# Dveri_Termotunnel_TRIAC.net
KiCad netlist of a schematic drawn in EAGLE
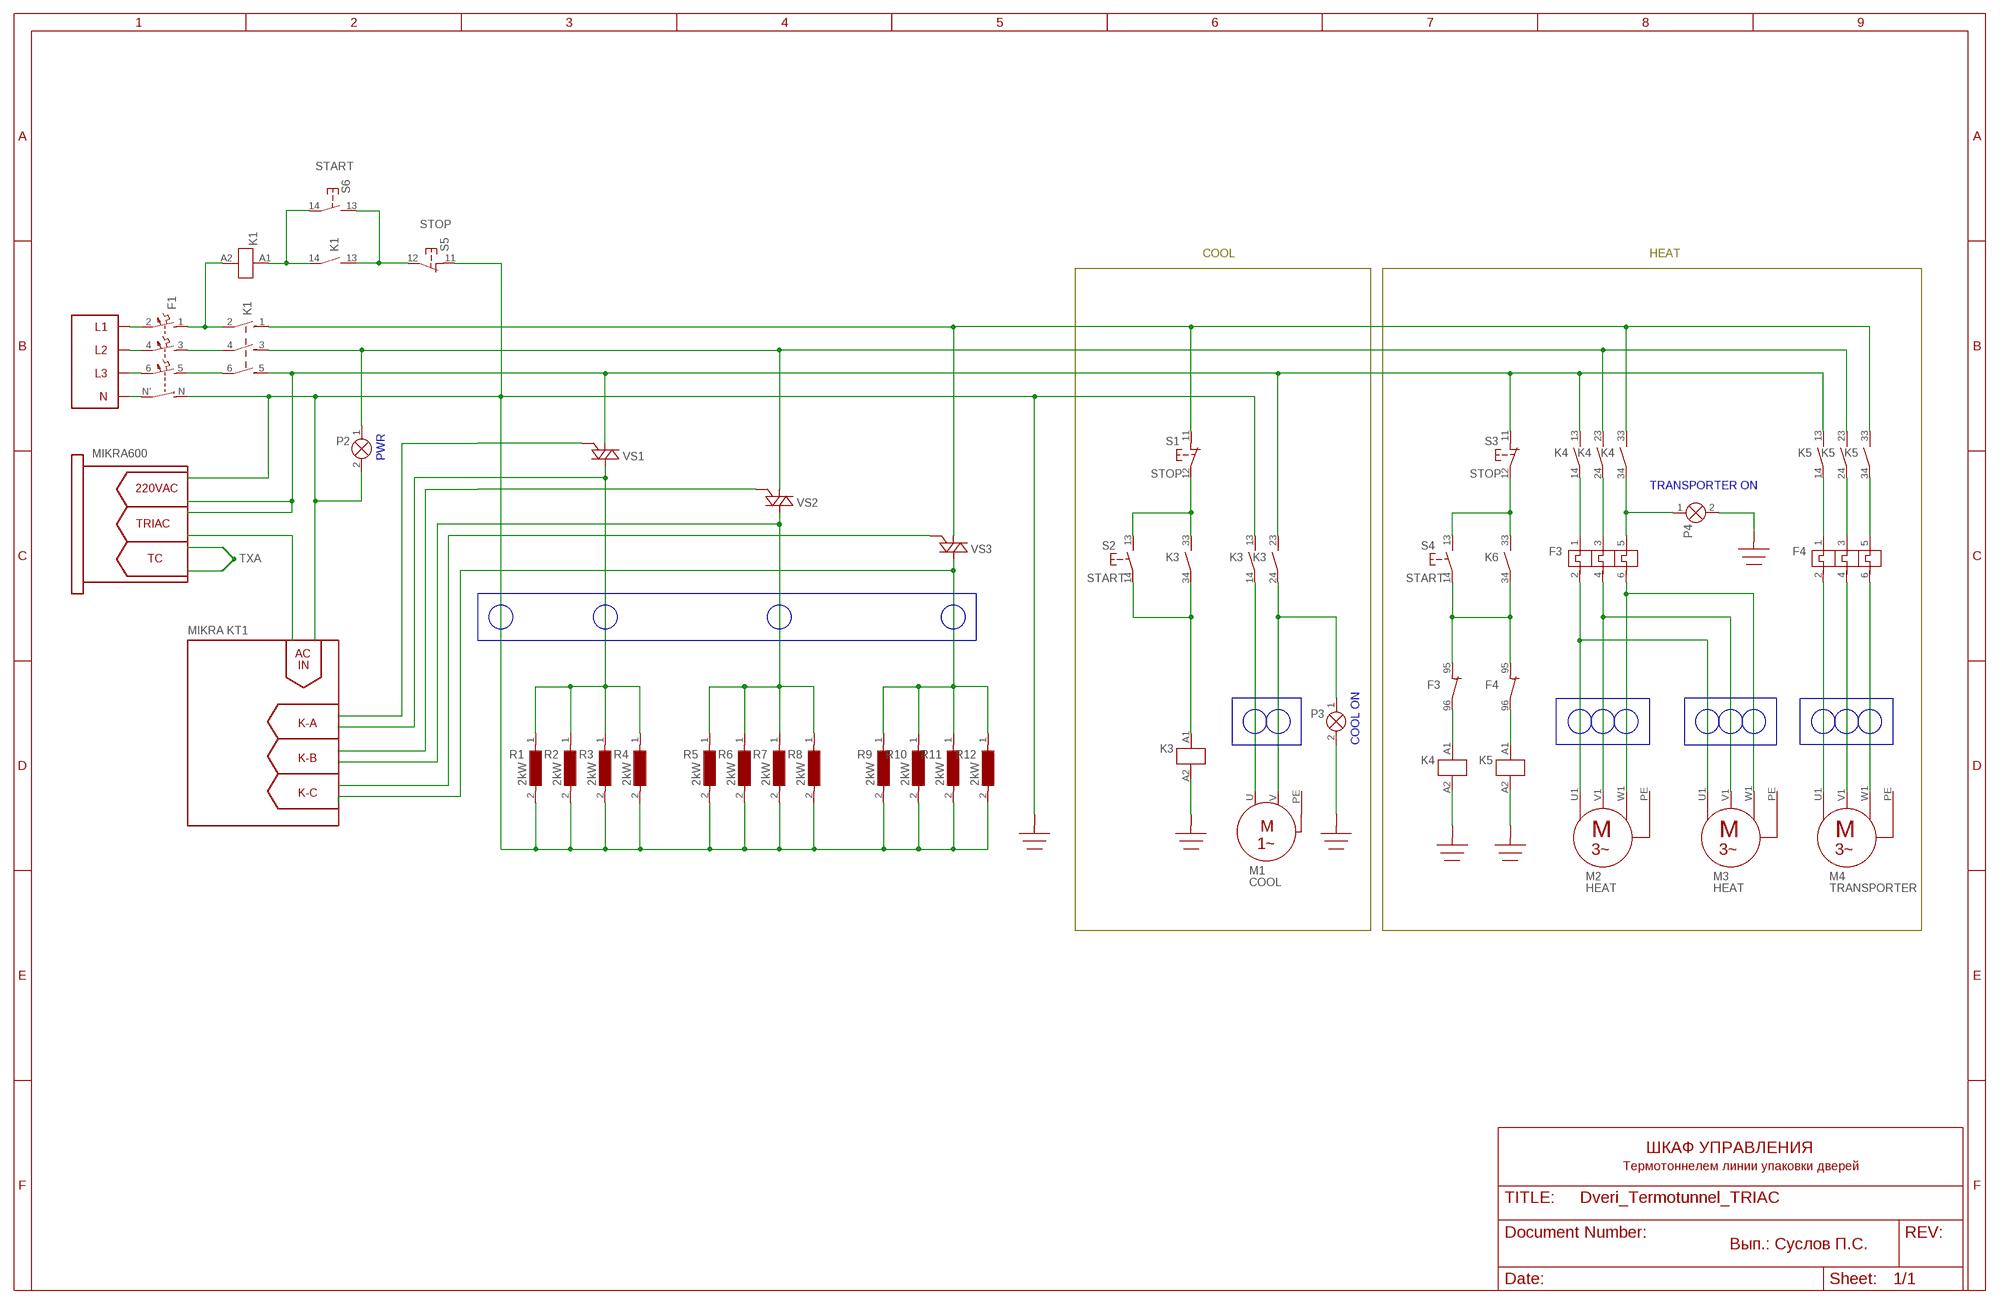
[diagram p0: schematic, sheet 1]

(export (version "E")
  (design (tool "Eeschema 10.0.6"))
  (components
    (comp (ref "F1")
      (value "LEITUNGSSCHUTZSCHALTER_4-POL")
      (footprint "eagle-import:LEITUNGSSCHUTZSCHALTER_4-POL")
      (libsource (lib "eagle-import") (part "LEITUNGSSCHUTZSCHALTER_4-POL"))
    )
    (comp (ref "F3")
      (value "MOTORSCHUTZSCHALTER_3-POL_THERM_AUSLOESUNG_HILFSKONTAKTE")
      (footprint "eagle-import:MOTORSCHUTZSCHALTER_3-POL_THERM_AUSLOESUNG_HILFSKONTAKT_95_96_97_98")
      (libsource (lib "eagle-import") (part "MOTORSCHUTZSCHALTER_3-POL_THERM_AUSLOESUNG_HILFSKONTAKTE"))
    )
    (comp (ref "F4")
      (value "MOTORSCHUTZSCHALTER_3-POL_THERM_AUSLOESUNG_HILFSKONTAKTE")
      (footprint "eagle-import:MOTORSCHUTZSCHALTER_3-POL_THERM_AUSLOESUNG_HILFSKONTAKT_95_96_97_98")
      (libsource (lib "eagle-import") (part "MOTORSCHUTZSCHALTER_3-POL_THERM_AUSLOESUNG_HILFSKONTAKTE"))
    )
    (comp (ref "K1")
      (value "HAUPTSCHUETZ_3-POL_HILFSKONTAKT_13-14")
      (footprint "eagle-import:HAUPTSCHUETZ_3-POL+HILFSKONTAKT_13-14")
      (libsource (lib "eagle-import") (part "HAUPTSCHUETZ_3-POL_HILFSKONTAKT_13-14"))
    )
    (comp (ref "K3")
      (value "HILFSSCHUETZ_13-14_23-24_33_34")
      (footprint "eagle-import:HILFSSCHUETZ_13-14_23-24_33_34")
      (libsource (lib "eagle-import") (part "HILFSSCHUETZ_13-14_23-24_33_34"))
    )
    (comp (ref "K4")
      (value "HILFSSCHUETZ_13-14_23-24_33_34")
      (footprint "eagle-import:HILFSSCHUETZ_13-14_23-24_33_34")
      (libsource (lib "eagle-import") (part "HILFSSCHUETZ_13-14_23-24_33_34"))
    )
    (comp (ref "K5")
      (value "HILFSSCHUETZ_13-14_23-24_33_34")
      (footprint "eagle-import:HILFSSCHUETZ_13-14_23-24_33_34")
      (libsource (lib "eagle-import") (part "HILFSSCHUETZ_13-14_23-24_33_34"))
    )
    (comp (ref "K6")
      (value "HILFSSCHUETZ_13-14_23-24_33_34")
      (footprint "eagle-import:HILFSSCHUETZ_13-14_23-24_33_34")
      (libsource (lib "eagle-import") (part "HILFSSCHUETZ_13-14_23-24_33_34"))
    )
    (comp (ref "M1")
      (value "COOL")
      (footprint "eagle-import:MOTOR_1-PHASEN")
      (libsource (lib "eagle-import") (part "MOTOR_1-PHASEN"))
    )
    (comp (ref "M2")
      (value "HEAT")
      (footprint "eagle-import:MOTOR_3-POL_PE")
      (libsource (lib "eagle-import") (part "MOTOR_3-POL_PE"))
    )
    (comp (ref "M3")
      (value "HEAT")
      (footprint "eagle-import:MOTOR_3-POL_PE")
      (libsource (lib "eagle-import") (part "MOTOR_3-POL_PE"))
    )
    (comp (ref "M4")
      (value "TRANSPORTER")
      (footprint "eagle-import:MOTOR_3-POL_PE")
      (libsource (lib "eagle-import") (part "MOTOR_3-POL_PE"))
    )
    (comp (ref "P2")
      (value "SIGNALLAMPE")
      (footprint "eagle-import:LAMPE")
      (libsource (lib "eagle-import") (part "SIGNALLAMPE"))
    )
    (comp (ref "P3")
      (value "SIGNALLAMPE")
      (footprint "eagle-import:LAMPE")
      (libsource (lib "eagle-import") (part "SIGNALLAMPE"))
    )
    (comp (ref "P4")
      (value "SIGNALLAMPE")
      (footprint "eagle-import:LAMPE")
      (libsource (lib "eagle-import") (part "SIGNALLAMPE"))
    )
    (comp (ref "R1")
      (value "2kW")
      (footprint "eagle-import:WICKLUNG")
      (libsource (lib "eagle-import") (part "SPULE"))
    )
    (comp (ref "R2")
      (value "2kW")
      (footprint "eagle-import:WICKLUNG")
      (libsource (lib "eagle-import") (part "SPULE"))
    )
    (comp (ref "R3")
      (value "2kW")
      (footprint "eagle-import:WICKLUNG")
      (libsource (lib "eagle-import") (part "SPULE"))
    )
    (comp (ref "R4")
      (value "2kW")
      (footprint "eagle-import:WICKLUNG")
      (libsource (lib "eagle-import") (part "SPULE"))
    )
    (comp (ref "R5")
      (value "2kW")
      (footprint "eagle-import:WICKLUNG")
      (libsource (lib "eagle-import") (part "SPULE"))
    )
    (comp (ref "R6")
      (value "2kW")
      (footprint "eagle-import:WICKLUNG")
      (libsource (lib "eagle-import") (part "SPULE"))
    )
    (comp (ref "R7")
      (value "2kW")
      (footprint "eagle-import:WICKLUNG")
      (libsource (lib "eagle-import") (part "SPULE"))
    )
    (comp (ref "R8")
      (value "2kW")
      (footprint "eagle-import:WICKLUNG")
      (libsource (lib "eagle-import") (part "SPULE"))
    )
    (comp (ref "R9")
      (value "2kW")
      (footprint "eagle-import:WICKLUNG")
      (libsource (lib "eagle-import") (part "SPULE"))
    )
    (comp (ref "R10")
      (value "2kW")
      (footprint "eagle-import:WICKLUNG")
      (libsource (lib "eagle-import") (part "SPULE"))
    )
    (comp (ref "R11")
      (value "2kW")
      (footprint "eagle-import:WICKLUNG")
      (libsource (lib "eagle-import") (part "SPULE"))
    )
    (comp (ref "R12")
      (value "2kW")
      (footprint "eagle-import:WICKLUNG")
      (libsource (lib "eagle-import") (part "SPULE"))
    )
    (comp (ref "S1")
      (value "OEFFNER_TASTSCHALTER")
      (footprint "eagle-import:OEFFNER_TASTSCHALTER")
      (libsource (lib "eagle-import") (part "OEFFNER_TASTSCHALTER"))
    )
    (comp (ref "S2")
      (value "SCHLIESSER_TASTSCHALTER")
      (footprint "eagle-import:SCHLIESSER_TASTSCHALTER")
      (libsource (lib "eagle-import") (part "SCHLIESSER_TASTSCHALTER"))
    )
    (comp (ref "S3")
      (value "OEFFNER_TASTSCHALTER")
      (footprint "eagle-import:OEFFNER_TASTSCHALTER")
      (libsource (lib "eagle-import") (part "OEFFNER_TASTSCHALTER"))
    )
    (comp (ref "S4")
      (value "SCHLIESSER_TASTSCHALTER")
      (footprint "eagle-import:SCHLIESSER_TASTSCHALTER")
      (libsource (lib "eagle-import") (part "SCHLIESSER_TASTSCHALTER"))
    )
    (comp (ref "S5")
      (value "OEFFNER_TASTSCHALTER")
      (footprint "eagle-import:OEFFNER_TASTSCHALTER")
      (libsource (lib "eagle-import") (part "OEFFNER_TASTSCHALTER"))
    )
    (comp (ref "S6")
      (value "SCHLIESSER_TASTSCHALTER")
      (footprint "eagle-import:SCHLIESSER_TASTSCHALTER")
      (libsource (lib "eagle-import") (part "SCHLIESSER_TASTSCHALTER"))
    )
    (comp (ref "VS1")
      (value "TRIAC")
      (footprint "eagle-import:TRIAC")
      (libsource (lib "eagle-import") (part "TRIAC"))
    )
    (comp (ref "VS2")
      (value "TRIAC")
      (footprint "eagle-import:TRIAC")
      (libsource (lib "eagle-import") (part "TRIAC"))
    )
    (comp (ref "VS3")
      (value "TRIAC")
      (footprint "eagle-import:TRIAC")
      (libsource (lib "eagle-import") (part "TRIAC"))
    )
    (comp (ref "X1")
      (value "ERDE_ALLGEMEIN")
      (footprint "eagle-import:ERDE_ALLGEMEIN")
      (libsource (lib "eagle-import") (part "ERDE_ALLGEMEIN"))
    )
    (comp (ref "X2")
      (value "ERDE_ALLGEMEIN")
      (footprint "eagle-import:ERDE_ALLGEMEIN")
      (libsource (lib "eagle-import") (part "ERDE_ALLGEMEIN"))
    )
    (comp (ref "X3")
      (value "ERDE_ALLGEMEIN")
      (footprint "eagle-import:ERDE_ALLGEMEIN")
      (libsource (lib "eagle-import") (part "ERDE_ALLGEMEIN"))
    )
    (comp (ref "X4")
      (value "ERDE_ALLGEMEIN")
      (footprint "eagle-import:ERDE_ALLGEMEIN")
      (libsource (lib "eagle-import") (part "ERDE_ALLGEMEIN"))
    )
    (comp (ref "X5")
      (value "ERDE_ALLGEMEIN")
      (footprint "eagle-import:ERDE_ALLGEMEIN")
      (libsource (lib "eagle-import") (part "ERDE_ALLGEMEIN"))
    )
    (comp (ref "X7")
      (value "ERDE_ALLGEMEIN")
      (footprint "eagle-import:ERDE_ALLGEMEIN")
      (libsource (lib "eagle-import") (part "ERDE_ALLGEMEIN"))
    )
  )
  (nets
    (net (code "1") (name "/N") (class "Default")
      (node (ref "F1") (pin "N") (pinfunction "N_N") (pintype "passive"))
      (node (ref "K3") (pin "13") (pinfunction "3_13") (pintype "passive"))
      (node (ref "K3") (pin "A2") (pinfunction "A2_A2") (pintype "input"))
      (node (ref "K4") (pin "A2") (pinfunction "A2_A2") (pintype "input"))
      (node (ref "K5") (pin "A2") (pinfunction "A2_A2") (pintype "input"))
      (node (ref "P2") (pin "2") (pinfunction "X2_2") (pintype "passive"))
      (node (ref "P3") (pin "2") (pinfunction "X2_2") (pintype "passive"))
      (node (ref "P4") (pin "2") (pinfunction "X2_2") (pintype "passive"))
      (node (ref "R1") (pin "2") (pinfunction "2_2") (pintype "passive"))
      (node (ref "R10") (pin "2") (pinfunction "2_2") (pintype "passive"))
      (node (ref "R11") (pin "2") (pinfunction "2_2") (pintype "passive"))
      (node (ref "R12") (pin "2") (pinfunction "2_2") (pintype "passive"))
      (node (ref "R2") (pin "2") (pinfunction "2_2") (pintype "passive"))
      (node (ref "R3") (pin "2") (pinfunction "2_2") (pintype "passive"))
      (node (ref "R4") (pin "2") (pinfunction "2_2") (pintype "passive"))
      (node (ref "R5") (pin "2") (pinfunction "2_2") (pintype "passive"))
      (node (ref "R6") (pin "2") (pinfunction "2_2") (pintype "passive"))
      (node (ref "R7") (pin "2") (pinfunction "2_2") (pintype "passive"))
      (node (ref "R8") (pin "2") (pinfunction "2_2") (pintype "passive"))
      (node (ref "R9") (pin "2") (pinfunction "2_2") (pintype "passive"))
      (node (ref "S5") (pin "11") (pinfunction "1_11") (pintype "input"))
      (node (ref "X1") (pin "1") (pinfunction "PE_1") (pintype "passive"))
      (node (ref "X2") (pin "1") (pinfunction "PE_1") (pintype "passive"))
      (node (ref "X3") (pin "1") (pinfunction "PE_1") (pintype "passive"))
      (node (ref "X4") (pin "1") (pinfunction "PE_1") (pintype "passive"))
      (node (ref "X5") (pin "1") (pinfunction "PE_1") (pintype "passive"))
      (node (ref "X7") (pin "1") (pinfunction "PE_1") (pintype "passive"))
    )
    (net (code "2") (name "Net-(F1-N-PadN')") (class "Default")
      (node (ref "F1") (pin "N'") (pinfunction "N_N'") (pintype "passive"))
    )
    (net (code "3") (name "Net-(F1-Pad1)") (class "Default")
      (node (ref "F1") (pin "1") (pinfunction "1_1") (pintype "passive"))
      (node (ref "K1") (pin "2") (pinfunction "2_2") (pintype "passive"))
      (node (ref "K1") (pin "A2") (pinfunction "A2_A2") (pintype "input"))
    )
    (net (code "4") (name "Net-(F1-Pad2)") (class "Default")
      (node (ref "F1") (pin "2") (pinfunction "2_2") (pintype "passive"))
    )
    (net (code "5") (name "Net-(F1-Pad3)") (class "Default")
      (node (ref "F1") (pin "3") (pinfunction "3_3") (pintype "passive"))
      (node (ref "K1") (pin "4") (pinfunction "4_4") (pintype "passive"))
    )
    (net (code "6") (name "Net-(F1-Pad4)") (class "Default")
      (node (ref "F1") (pin "4") (pinfunction "4_4") (pintype "passive"))
    )
    (net (code "7") (name "Net-(F1-Pad5)") (class "Default")
      (node (ref "F1") (pin "5") (pinfunction "5_5") (pintype "passive"))
      (node (ref "K1") (pin "6") (pinfunction "6_6") (pintype "passive"))
    )
    (net (code "8") (name "Net-(F1-Pad6)") (class "Default")
      (node (ref "F1") (pin "6") (pinfunction "6_6") (pintype "passive"))
    )
    (net (code "9") (name "Net-(F3-Pad2)") (class "Default")
      (node (ref "F3") (pin "2") (pinfunction "2_2") (pintype "passive"))
      (node (ref "M2") (pin "U1") (pinfunction "U1_U1") (pintype "passive"))
      (node (ref "M3") (pin "U1") (pinfunction "U1_U1") (pintype "passive"))
    )
    (net (code "10") (name "Net-(F3-Pad4)") (class "Default")
      (node (ref "F3") (pin "4") (pinfunction "4_4") (pintype "passive"))
      (node (ref "M2") (pin "V1") (pinfunction "V1_V1") (pintype "passive"))
      (node (ref "M3") (pin "V1") (pinfunction "V1_V1") (pintype "passive"))
    )
    (net (code "11") (name "Net-(F3-Pad6)") (class "Default")
      (node (ref "F3") (pin "6") (pinfunction "6_6") (pintype "passive"))
      (node (ref "M2") (pin "W1") (pinfunction "W1_W1") (pintype "passive"))
      (node (ref "M3") (pin "W1") (pinfunction "W1_W1") (pintype "passive"))
    )
    (net (code "12") (name "Net-(F3-Pad96)") (class "Default")
      (node (ref "F3") (pin "96") (pinfunction "96_96") (pintype "passive"))
      (node (ref "K4") (pin "A1") (pinfunction "A1_A1") (pintype "input"))
    )
    (net (code "13") (name "Net-(F4-Pad2)") (class "Default")
      (node (ref "F4") (pin "2") (pinfunction "2_2") (pintype "passive"))
      (node (ref "M4") (pin "U1") (pinfunction "U1_U1") (pintype "passive"))
    )
    (net (code "14") (name "Net-(F4-Pad4)") (class "Default")
      (node (ref "F4") (pin "4") (pinfunction "4_4") (pintype "passive"))
      (node (ref "M4") (pin "V1") (pinfunction "V1_V1") (pintype "passive"))
    )
    (net (code "15") (name "Net-(F4-Pad6)") (class "Default")
      (node (ref "F4") (pin "6") (pinfunction "6_6") (pintype "passive"))
      (node (ref "M4") (pin "W1") (pinfunction "W1_W1") (pintype "passive"))
    )
    (net (code "16") (name "Net-(F4-Pad96)") (class "Default")
      (node (ref "F4") (pin "96") (pinfunction "96_96") (pintype "passive"))
      (node (ref "K5") (pin "A1") (pinfunction "A1_A1") (pintype "input"))
    )
    (net (code "17") (name "Net-(K1B-3)") (class "Default")
      (node (ref "K1") (pin "13") (pinfunction "3_13") (pintype "passive"))
      (node (ref "S5") (pin "12") (pinfunction "2_12") (pintype "input"))
      (node (ref "S6") (pin "13") (pinfunction "3_13") (pintype "input"))
    )
    (net (code "18") (name "Net-(K1B-4)") (class "Default")
      (node (ref "K1") (pin "14") (pinfunction "4_14") (pintype "passive"))
      (node (ref "K1") (pin "A1") (pinfunction "A1_A1") (pintype "input"))
      (node (ref "S6") (pin "14") (pinfunction "4_14") (pintype "input"))
    )
    (net (code "19") (name "Net-(K3A-4)") (class "Default")
      (node (ref "K3") (pin "14") (pinfunction "4_14") (pintype "passive"))
      (node (ref "M1") (pin "U") (pinfunction "U_U") (pintype "passive"))
    )
    (net (code "20") (name "Net-(K3B-3)") (class "Default")
      (node (ref "K1") (pin "5") (pinfunction "5_5") (pintype "passive"))
      (node (ref "K3") (pin "23") (pinfunction "3_23") (pintype "passive"))
      (node (ref "K4") (pin "13") (pinfunction "3_13") (pintype "passive"))
      (node (ref "K5") (pin "13") (pinfunction "3_13") (pintype "passive"))
      (node (ref "S3") (pin "11") (pinfunction "1_11") (pintype "input"))
      (node (ref "VS1") (pin "A2") (pinfunction "A2_A2") (pintype "passive"))
    )
    (net (code "21") (name "Net-(K3B-4)") (class "Default")
      (node (ref "K3") (pin "24") (pinfunction "4_24") (pintype "passive"))
      (node (ref "M1") (pin "V") (pinfunction "V_V") (pintype "passive"))
      (node (ref "P3") (pin "1") (pinfunction "X1_1") (pintype "passive"))
    )
    (net (code "22") (name "Net-(K3C-3)") (class "Default")
      (node (ref "K3") (pin "33") (pinfunction "3_33") (pintype "passive"))
      (node (ref "S1") (pin "12") (pinfunction "2_12") (pintype "input"))
      (node (ref "S2") (pin "13") (pinfunction "3_13") (pintype "input"))
    )
    (net (code "23") (name "Net-(K3C-4)") (class "Default")
      (node (ref "K3") (pin "34") (pinfunction "4_34") (pintype "passive"))
      (node (ref "K3") (pin "A1") (pinfunction "A1_A1") (pintype "input"))
      (node (ref "S2") (pin "14") (pinfunction "4_14") (pintype "input"))
    )
    (net (code "24") (name "Net-(K4A-4)") (class "Default")
      (node (ref "F3") (pin "1") (pinfunction "1_1") (pintype "passive"))
      (node (ref "K4") (pin "14") (pinfunction "4_14") (pintype "passive"))
    )
    (net (code "25") (name "Net-(K4B-3)") (class "Default")
      (node (ref "K1") (pin "3") (pinfunction "3_3") (pintype "passive"))
      (node (ref "K4") (pin "23") (pinfunction "3_23") (pintype "passive"))
      (node (ref "K5") (pin "23") (pinfunction "3_23") (pintype "passive"))
      (node (ref "P2") (pin "1") (pinfunction "X1_1") (pintype "passive"))
      (node (ref "VS2") (pin "A2") (pinfunction "A2_A2") (pintype "passive"))
    )
    (net (code "26") (name "Net-(K4B-4)") (class "Default")
      (node (ref "F3") (pin "3") (pinfunction "3_3") (pintype "passive"))
      (node (ref "K4") (pin "24") (pinfunction "4_24") (pintype "passive"))
    )
    (net (code "27") (name "Net-(K4C-3)") (class "Default")
      (node (ref "K1") (pin "1") (pinfunction "1_1") (pintype "passive"))
      (node (ref "K4") (pin "33") (pinfunction "3_33") (pintype "passive"))
      (node (ref "K5") (pin "33") (pinfunction "3_33") (pintype "passive"))
      (node (ref "S1") (pin "11") (pinfunction "1_11") (pintype "input"))
      (node (ref "VS3") (pin "A2") (pinfunction "A2_A2") (pintype "passive"))
    )
    (net (code "28") (name "Net-(K4C-4)") (class "Default")
      (node (ref "F3") (pin "5") (pinfunction "5_5") (pintype "passive"))
      (node (ref "K4") (pin "34") (pinfunction "4_34") (pintype "passive"))
      (node (ref "P4") (pin "1") (pinfunction "X1_1") (pintype "passive"))
    )
    (net (code "29") (name "Net-(K5A-4)") (class "Default")
      (node (ref "F4") (pin "1") (pinfunction "1_1") (pintype "passive"))
      (node (ref "K5") (pin "14") (pinfunction "4_14") (pintype "passive"))
    )
    (net (code "30") (name "Net-(K5B-4)") (class "Default")
      (node (ref "F4") (pin "3") (pinfunction "3_3") (pintype "passive"))
      (node (ref "K5") (pin "24") (pinfunction "4_24") (pintype "passive"))
    )
    (net (code "31") (name "Net-(K5C-4)") (class "Default")
      (node (ref "F4") (pin "5") (pinfunction "5_5") (pintype "passive"))
      (node (ref "K5") (pin "34") (pinfunction "4_34") (pintype "passive"))
    )
    (net (code "32") (name "Net-(K6C-3)") (class "Default")
      (node (ref "K6") (pin "33") (pinfunction "3_33") (pintype "passive"))
      (node (ref "S3") (pin "12") (pinfunction "2_12") (pintype "input"))
      (node (ref "S4") (pin "13") (pinfunction "3_13") (pintype "input"))
    )
    (net (code "33") (name "Net-(K6C-4)") (class "Default")
      (node (ref "F3") (pin "95") (pinfunction "95_95") (pintype "passive"))
      (node (ref "F4") (pin "95") (pinfunction "95_95") (pintype "passive"))
      (node (ref "K6") (pin "34") (pinfunction "4_34") (pintype "passive"))
      (node (ref "S4") (pin "14") (pinfunction "4_14") (pintype "input"))
    )
    (net (code "34") (name "Net-(R1-Pad1)") (class "Default")
      (node (ref "R1") (pin "1") (pinfunction "1_1") (pintype "passive"))
      (node (ref "R2") (pin "1") (pinfunction "1_1") (pintype "passive"))
      (node (ref "R3") (pin "1") (pinfunction "1_1") (pintype "passive"))
      (node (ref "R4") (pin "1") (pinfunction "1_1") (pintype "passive"))
      (node (ref "VS1") (pin "A1") (pinfunction "A1_A1") (pintype "passive"))
    )
    (net (code "35") (name "Net-(R5-Pad1)") (class "Default")
      (node (ref "R5") (pin "1") (pinfunction "1_1") (pintype "passive"))
      (node (ref "R6") (pin "1") (pinfunction "1_1") (pintype "passive"))
      (node (ref "R7") (pin "1") (pinfunction "1_1") (pintype "passive"))
      (node (ref "R8") (pin "1") (pinfunction "1_1") (pintype "passive"))
      (node (ref "VS2") (pin "A1") (pinfunction "A1_A1") (pintype "passive"))
    )
    (net (code "36") (name "Net-(R10-Pad1)") (class "Default")
      (node (ref "R10") (pin "1") (pinfunction "1_1") (pintype "passive"))
      (node (ref "R11") (pin "1") (pinfunction "1_1") (pintype "passive"))
      (node (ref "R12") (pin "1") (pinfunction "1_1") (pintype "passive"))
      (node (ref "R9") (pin "1") (pinfunction "1_1") (pintype "passive"))
      (node (ref "VS3") (pin "A1") (pinfunction "A1_A1") (pintype "passive"))
    )
    (net (code "37") (name "unconnected-(M1-PadPE)") (class "Default")
      (node (ref "M1") (pin "PE") (pinfunction "PE_PE") (pintype "passive"))
    )
    (net (code "38") (name "unconnected-(M2-PadPE)") (class "Default")
      (node (ref "M2") (pin "PE") (pinfunction "PE_PE") (pintype "passive"))
    )
    (net (code "39") (name "unconnected-(M3-PadPE)") (class "Default")
      (node (ref "M3") (pin "PE") (pinfunction "PE_PE") (pintype "passive"))
    )
    (net (code "40") (name "unconnected-(M4-PadPE)") (class "Default")
      (node (ref "M4") (pin "PE") (pinfunction "PE_PE") (pintype "passive"))
    )
    (net (code "41") (name "unconnected-(VS1-PadG)") (class "Default")
      (node (ref "VS1") (pin "G") (pinfunction "G_G") (pintype "passive"))
    )
    (net (code "42") (name "unconnected-(VS2-PadG)") (class "Default")
      (node (ref "VS2") (pin "G") (pinfunction "G_G") (pintype "passive"))
    )
    (net (code "43") (name "unconnected-(VS3-PadG)") (class "Default")
      (node (ref "VS3") (pin "G") (pinfunction "G_G") (pintype "passive"))
    )
  )
)
